# Knee_Comp_Clipper.net
KiCad netlist of a schematic drawn in Altium Designer
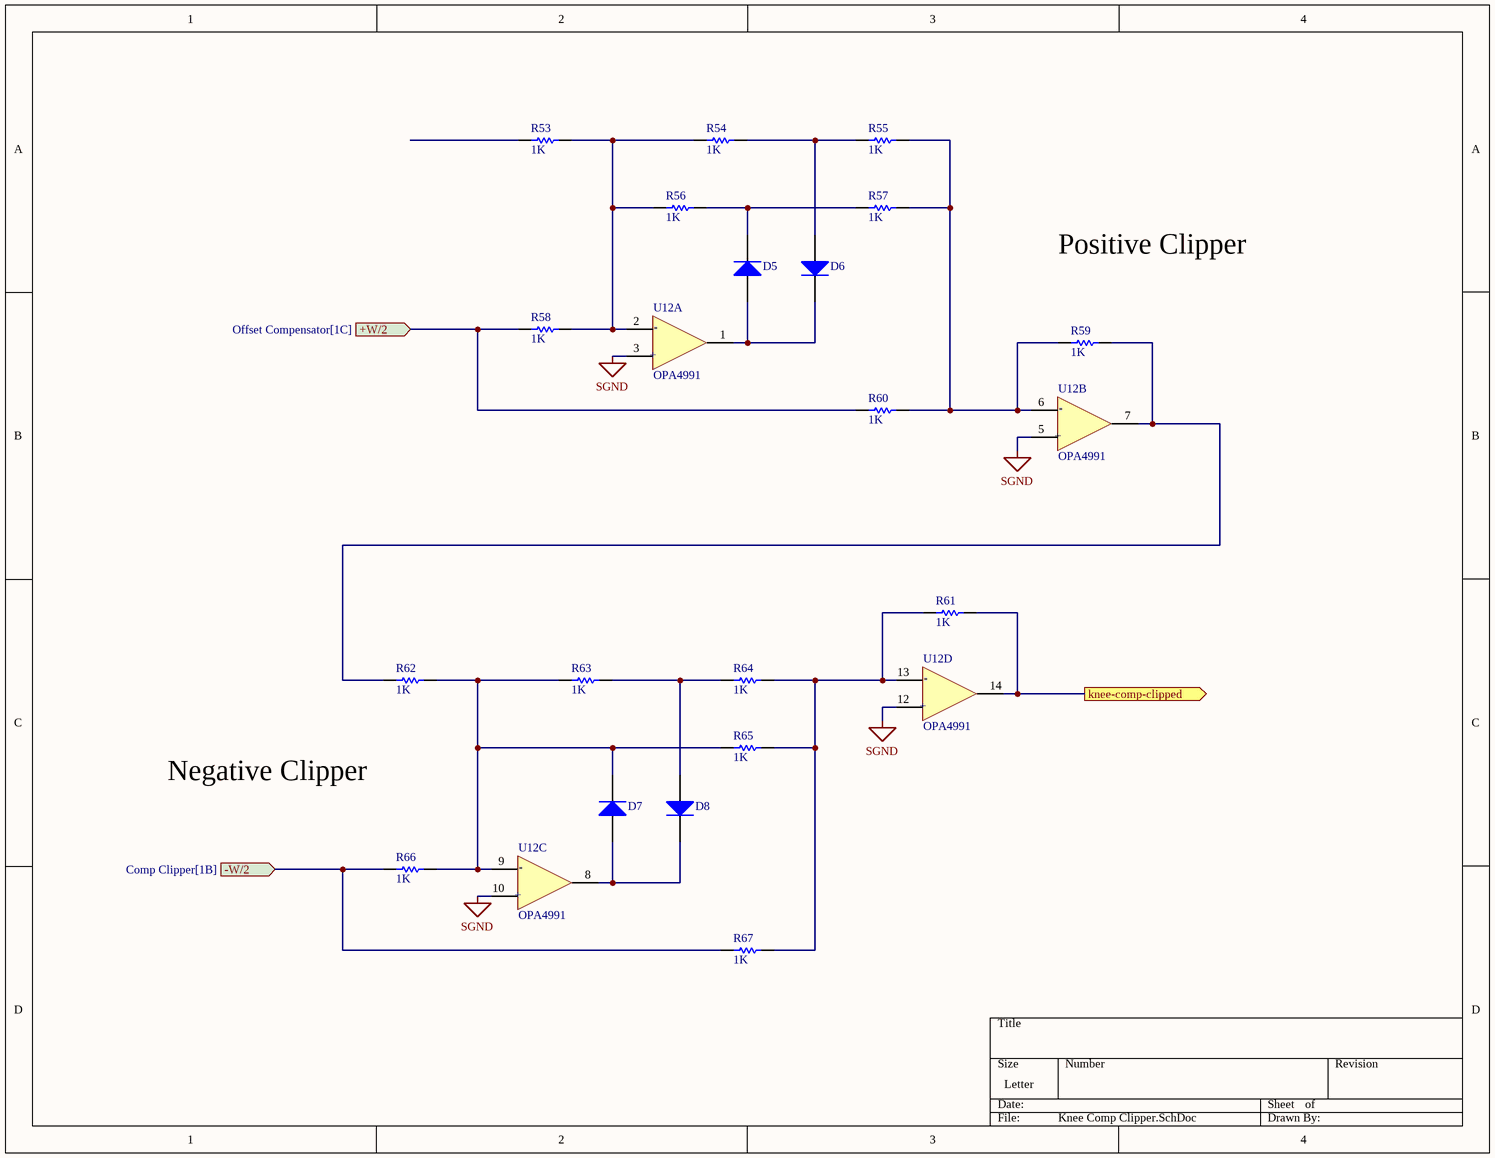
[diagram p0: Knee Comp Clipper.SchDoc]

(export (version "E")
  (design (tool "Eeschema 10.0.6"))
  (components
    (comp (ref "D5") (value "Diode") (libsource (lib "Simulation Generic Components") (part "Diode")))
    (comp (ref "D6") (value "Diode") (libsource (lib "Simulation Generic Components") (part "Diode")))
    (comp (ref "D7") (value "Diode") (libsource (lib "Simulation Generic Components") (part "Diode")))
    (comp (ref "D8") (value "Diode") (libsource (lib "Simulation Generic Components") (part "Diode")))
    (comp (ref "R53")
      (value "1K")
      (description "Resistor")
      (libsource (lib "Simulation Generic Components") (part "Resistor"))
    )
    (comp (ref "R54")
      (value "1K")
      (description "Resistor")
      (libsource (lib "Simulation Generic Components") (part "Resistor"))
    )
    (comp (ref "R55")
      (value "1K")
      (description "Resistor")
      (libsource (lib "Simulation Generic Components") (part "Resistor"))
    )
    (comp (ref "R56")
      (value "1K")
      (description "Resistor")
      (libsource (lib "Simulation Generic Components") (part "Resistor"))
    )
    (comp (ref "R57")
      (value "1K")
      (description "Resistor")
      (libsource (lib "Simulation Generic Components") (part "Resistor"))
    )
    (comp (ref "R58")
      (value "1K")
      (description "Resistor")
      (libsource (lib "Simulation Generic Components") (part "Resistor"))
    )
    (comp (ref "R59")
      (value "1K")
      (description "Resistor")
      (libsource (lib "Simulation Generic Components") (part "Resistor"))
    )
    (comp (ref "R60")
      (value "1K")
      (description "Resistor")
      (libsource (lib "Simulation Generic Components") (part "Resistor"))
    )
    (comp (ref "R61")
      (value "1K")
      (description "Resistor")
      (libsource (lib "Simulation Generic Components") (part "Resistor"))
    )
    (comp (ref "R62")
      (value "1K")
      (description "Resistor")
      (libsource (lib "Simulation Generic Components") (part "Resistor"))
    )
    (comp (ref "R63")
      (value "1K")
      (description "Resistor")
      (libsource (lib "Simulation Generic Components") (part "Resistor"))
    )
    (comp (ref "R64")
      (value "1K")
      (description "Resistor")
      (libsource (lib "Simulation Generic Components") (part "Resistor"))
    )
    (comp (ref "R65")
      (value "1K")
      (description "Resistor")
      (libsource (lib "Simulation Generic Components") (part "Resistor"))
    )
    (comp (ref "R66")
      (value "1K")
      (description "Resistor")
      (libsource (lib "Simulation Generic Components") (part "Resistor"))
    )
    (comp (ref "R67")
      (value "1K")
      (description "Resistor")
      (libsource (lib "Simulation Generic Components") (part "Resistor"))
    )
    (comp (ref "U12")
      (value "OPA4991")
      (footprint "FP-D0014A-IPC_B")
      (description "40-V, DUAL 4.5MHZ, RAIL-TO-RAIL")
      (libsource (lib "DRC") (part "OPA4991IDR"))
    )
  )
  (nets
    (net (code "1") (name "/+W{slash}2") (class "Default")
      (node (ref "R58") (pin "1") (pinfunction "1_1") (pintype "passive"))
      (node (ref "R60") (pin "1") (pinfunction "1_1") (pintype "passive"))
    )
    (net (code "2") (name "/-W{slash}2") (class "Default")
      (node (ref "R66") (pin "1") (pinfunction "1_1") (pintype "passive"))
      (node (ref "R67") (pin "1") (pinfunction "1_1") (pintype "passive"))
    )
    (net (code "3") (name "/knee-comp-clipped") (class "Default")
      (node (ref "R61") (pin "2") (pinfunction "2_2") (pintype "passive"))
      (node (ref "U12") (pin "14") (pinfunction "OUT4_14") (pintype "passive"))
    )
    (net (code "4") (name "Net-(D5-A)") (class "Default")
      (node (ref "D5") (pin "1") (pinfunction "A_1") (pintype "passive"))
      (node (ref "D6") (pin "2") (pinfunction "K_2") (pintype "passive"))
      (node (ref "U12") (pin "1") (pinfunction "OUT1_1") (pintype "passive"))
    )
    (net (code "5") (name "Net-(D5-K)") (class "Default")
      (node (ref "D5") (pin "2") (pinfunction "K_2") (pintype "passive"))
      (node (ref "R56") (pin "2") (pinfunction "2_2") (pintype "passive"))
      (node (ref "R57") (pin "1") (pinfunction "1_1") (pintype "passive"))
    )
    (net (code "6") (name "Net-(D6-A)") (class "Default")
      (node (ref "D6") (pin "1") (pinfunction "A_1") (pintype "passive"))
      (node (ref "R54") (pin "2") (pinfunction "2_2") (pintype "passive"))
      (node (ref "R55") (pin "1") (pinfunction "1_1") (pintype "passive"))
    )
    (net (code "7") (name "Net-(D7-A)") (class "Default")
      (node (ref "D7") (pin "1") (pinfunction "A_1") (pintype "passive"))
      (node (ref "D8") (pin "2") (pinfunction "K_2") (pintype "passive"))
      (node (ref "U12") (pin "8") (pinfunction "OUT3_8") (pintype "passive"))
    )
    (net (code "8") (name "Net-(D7-K)") (class "Default")
      (node (ref "D7") (pin "2") (pinfunction "K_2") (pintype "passive"))
      (node (ref "R62") (pin "2") (pinfunction "2_2") (pintype "passive"))
      (node (ref "R63") (pin "1") (pinfunction "1_1") (pintype "passive"))
      (node (ref "R65") (pin "1") (pinfunction "1_1") (pintype "passive"))
      (node (ref "R66") (pin "2") (pinfunction "2_2") (pintype "passive"))
      (node (ref "U12") (pin "9") (pinfunction "IN3-_9") (pintype "tri_state"))
    )
    (net (code "9") (name "Net-(D8-A)") (class "Default")
      (node (ref "D8") (pin "1") (pinfunction "A_1") (pintype "passive"))
      (node (ref "R63") (pin "2") (pinfunction "2_2") (pintype "passive"))
      (node (ref "R64") (pin "1") (pinfunction "1_1") (pintype "passive"))
    )
    (net (code "10") (name "Net-(U12A-IN1-)") (class "Default")
      (node (ref "R53") (pin "2") (pinfunction "2_2") (pintype "passive"))
      (node (ref "R54") (pin "1") (pinfunction "1_1") (pintype "passive"))
      (node (ref "R56") (pin "1") (pinfunction "1_1") (pintype "passive"))
      (node (ref "R58") (pin "2") (pinfunction "2_2") (pintype "passive"))
      (node (ref "U12") (pin "2") (pinfunction "IN1-_2") (pintype "tri_state"))
    )
    (net (code "11") (name "Net-(U12B-IN2-)") (class "Default")
      (node (ref "R55") (pin "2") (pinfunction "2_2") (pintype "passive"))
      (node (ref "R57") (pin "2") (pinfunction "2_2") (pintype "passive"))
      (node (ref "R59") (pin "1") (pinfunction "1_1") (pintype "passive"))
      (node (ref "R60") (pin "2") (pinfunction "2_2") (pintype "passive"))
      (node (ref "U12") (pin "6") (pinfunction "IN2-_6") (pintype "tri_state"))
    )
    (net (code "12") (name "Net-(U12B-OUT2)") (class "Default")
      (node (ref "R59") (pin "2") (pinfunction "2_2") (pintype "passive"))
      (node (ref "R62") (pin "1") (pinfunction "1_1") (pintype "passive"))
      (node (ref "U12") (pin "7") (pinfunction "OUT2_7") (pintype "passive"))
    )
    (net (code "13") (name "Net-(U12D-IN4-)") (class "Default")
      (node (ref "R61") (pin "1") (pinfunction "1_1") (pintype "passive"))
      (node (ref "R64") (pin "2") (pinfunction "2_2") (pintype "passive"))
      (node (ref "R65") (pin "2") (pinfunction "2_2") (pintype "passive"))
      (node (ref "R67") (pin "2") (pinfunction "2_2") (pintype "passive"))
      (node (ref "U12") (pin "13") (pinfunction "IN4-_13") (pintype "tri_state"))
    )
    (net (code "14") (name "SGND") (class "Default")
      (node (ref "U12") (pin "10") (pinfunction "IN3+_10") (pintype "tri_state"))
      (node (ref "U12") (pin "12") (pinfunction "IN4+_12") (pintype "tri_state"))
      (node (ref "U12") (pin "3") (pinfunction "IN1+_3") (pintype "tri_state"))
      (node (ref "U12") (pin "5") (pinfunction "IN2+_5") (pintype "tri_state"))
    )
    (net (code "15") (name "unconnected-(R53-Pad1)") (class "Default")
      (node (ref "R53") (pin "1") (pinfunction "1_1") (pintype "passive"))
    )
  )
)
